# Stacked_Pot_Breakout.net
KiCad netlist of a schematic drawn in Altium Designer
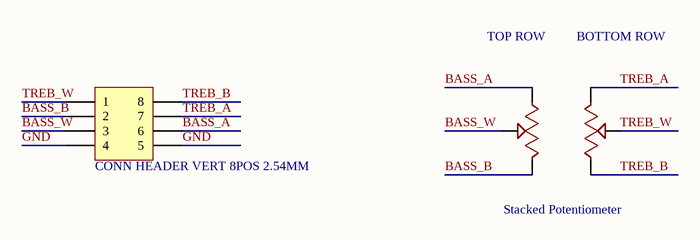
[diagram p0: Stacked_Pot_Breakout.SchDoc]

(export (version "E")
  (design (tool "Eeschema 10.0.6"))
  (components
    (comp (ref "J1")
      (value "CONN HEADER VERT 8POS 2.54MM")
      (footprint "CONN HEADER VERT 8POS 2.54MM")
      (description "Connector Header Through Hole 8 position 0.100\" (2.54mm)")
      (fields (field (name "MANUFACTURER") "Samtec Inc.") (field (name "DIGIKEY PART NUMBER") "SAM8996-ND"))
      (libsource (lib "GuitarLibrary") (part "CONN HEADER VERT 8POS 2.54MM"))
    )
    (comp (ref "VR1")
      (value "Stacked Potentiometer")
      (footprint "STACKED POTENTIOMETER")
      (libsource (lib "GuitarLibrary") (part "Stacked Potentiometer"))
    )
  )
  (nets
    (net (code "1") (name "/BASS_A") (class "Default")
      (node (ref "J1") (pin "6") (pinfunction "6_6") (pintype "passive"))
      (node (ref "VR1") (pin "1") (pinfunction "A1_1") (pintype "passive"))
    )
    (net (code "2") (name "/BASS_B") (class "Default")
      (node (ref "J1") (pin "2") (pinfunction "2_2") (pintype "passive"))
      (node (ref "VR1") (pin "3") (pinfunction "B1_3") (pintype "passive"))
    )
    (net (code "3") (name "/BASS_W") (class "Default")
      (node (ref "J1") (pin "3") (pinfunction "3_3") (pintype "passive"))
      (node (ref "VR1") (pin "2") (pinfunction "W1_2") (pintype "passive"))
    )
    (net (code "4") (name "/GND") (class "Default")
      (node (ref "J1") (pin "4") (pinfunction "4_4") (pintype "passive"))
      (node (ref "J1") (pin "5") (pinfunction "5_5") (pintype "passive"))
    )
    (net (code "5") (name "/TREB_A") (class "Default")
      (node (ref "J1") (pin "7") (pinfunction "7_7") (pintype "passive"))
      (node (ref "VR1") (pin "6") (pinfunction "A2_6") (pintype "passive"))
    )
    (net (code "6") (name "/TREB_B") (class "Default")
      (node (ref "J1") (pin "8") (pinfunction "8_8") (pintype "passive"))
      (node (ref "VR1") (pin "4") (pinfunction "B2_4") (pintype "passive"))
    )
    (net (code "7") (name "/TREB_W") (class "Default")
      (node (ref "J1") (pin "1") (pinfunction "1_1") (pintype "passive"))
      (node (ref "VR1") (pin "5") (pinfunction "W2_5") (pintype "passive"))
    )
  )
)
